# DM1097_IMX378.net
KiCad netlist of a schematic drawn in Altium Designer
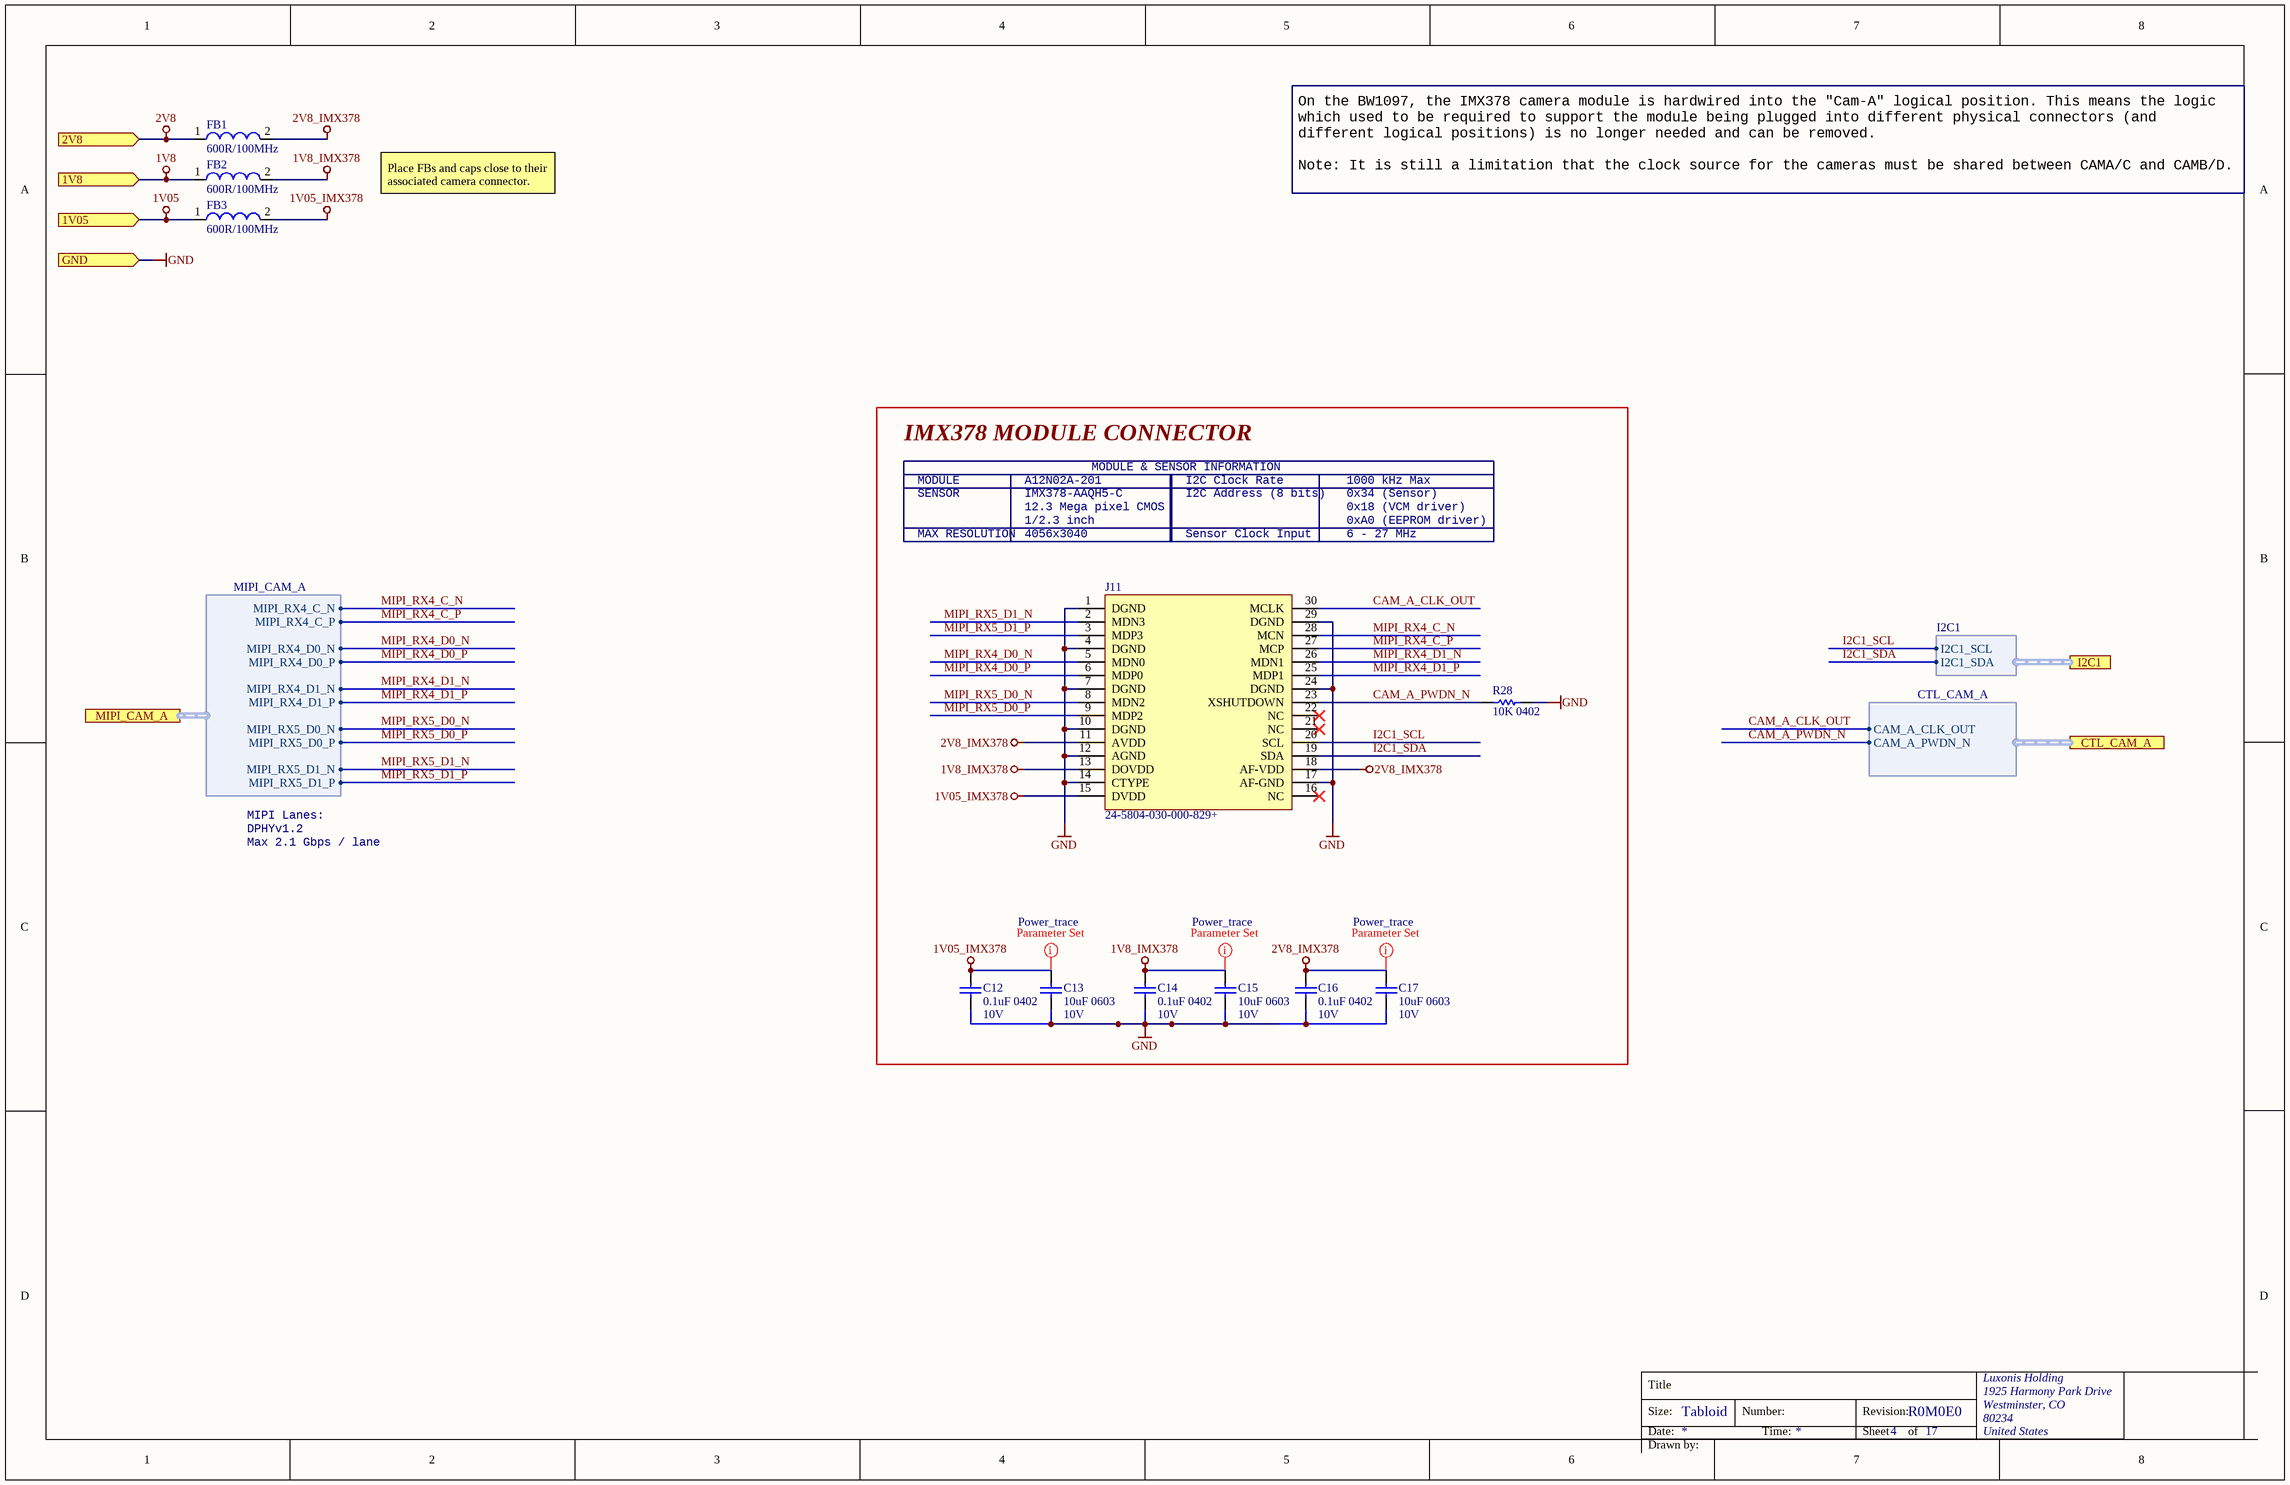
[diagram p0: DM1097_IMX378.SchDoc]

(export (version "E")
  (design (tool "Eeschema 10.0.6"))
  (components
    (comp (ref "C12")
      (value "0.1uF 0402")
      (footprint "CAP_Altium_Vault_Generic:CAPC0402(1005)70_N")
      (description "CAP CER 0.1UF 10V X7R 0402 5%")
      (fields (field (name "TOLERANCE") "5%") (field (name "VOLTAGE RATING") "10V"))
      (libsource (lib "LuxonisMaster") (part "GRM155R71A104JA01D"))
    )
    (comp (ref "C13")
      (value "10uF 0603")
      (footprint "CAP_Altium_Vault_Generic:CAPC0603(1608)100_N")
      (description "CAP CER 10UF 10V X5R 0603 20%")
      (fields (field (name "TOLERANCE") "20%") (field (name "VOLTAGE RATING") "10V"))
      (libsource (lib "LuxonisMaster") (part "GRM188R61A106ME69D"))
    )
    (comp (ref "C14")
      (value "0.1uF 0402")
      (footprint "CAP_Altium_Vault_Generic:CAPC0402(1005)70_N")
      (description "CAP CER 0.1UF 10V X7R 0402 5%")
      (fields (field (name "TOLERANCE") "5%") (field (name "VOLTAGE RATING") "10V"))
      (libsource (lib "LuxonisMaster") (part "GRM155R71A104JA01D"))
    )
    (comp (ref "C15")
      (value "10uF 0603")
      (footprint "CAP_Altium_Vault_Generic:CAPC0603(1608)100_N")
      (description "CAP CER 10UF 10V X5R 0603 20%")
      (fields (field (name "TOLERANCE") "20%") (field (name "VOLTAGE RATING") "10V"))
      (libsource (lib "LuxonisMaster") (part "GRM188R61A106ME69D"))
    )
    (comp (ref "C16")
      (value "0.1uF 0402")
      (footprint "CAP_Altium_Vault_Generic:CAPC0402(1005)70_N")
      (description "CAP CER 0.1UF 10V X7R 0402 5%")
      (fields (field (name "TOLERANCE") "5%") (field (name "VOLTAGE RATING") "10V"))
      (libsource (lib "LuxonisMaster") (part "GRM155R71A104JA01D"))
    )
    (comp (ref "C17")
      (value "10uF 0603")
      (footprint "CAP_Altium_Vault_Generic:CAPC0603(1608)100_N")
      (description "CAP CER 10UF 10V X5R 0603 20%")
      (fields (field (name "TOLERANCE") "20%") (field (name "VOLTAGE RATING") "10V"))
      (libsource (lib "LuxonisMaster") (part "GRM188R61A106ME69D"))
    )
    (comp (ref "FB1")
      (value "600R/100MHz")
      (footprint "LuxonisMaster:2508056017Y2")
      (description "FERRITE BEAD, 0.1OHM, 2A, 0805, 600R/100MHz")
      (fields (field (name "TOLERANCE") "25%"))
      (libsource (lib "LuxonisMaster") (part "2508056017Y2"))
    )
    (comp (ref "FB2")
      (value "600R/100MHz")
      (footprint "LuxonisMaster:2508056017Y2")
      (description "FERRITE BEAD, 0.1OHM, 2A, 0805, 600R/100MHz")
      (fields (field (name "TOLERANCE") "25%"))
      (libsource (lib "LuxonisMaster") (part "2508056017Y2"))
    )
    (comp (ref "FB3")
      (value "600R/100MHz")
      (footprint "LuxonisMaster:2508056017Y2")
      (description "FERRITE BEAD, 0.1OHM, 2A, 0805, 600R/100MHz")
      (fields (field (name "TOLERANCE") "25%"))
      (libsource (lib "LuxonisMaster") (part "2508056017Y2"))
    )
    (comp (ref "J11")
      (value "24-5804-030-000-829+")
      (footprint "LuxonisMaster:A12N02A-201_MatedModule")
      (description "CONN Series 5804 board to board 0.4mm pitch 30 way connector")
      (libsource (lib "LuxonisMaster") (part "A12N02A-201_Connector"))
    )
    (comp (ref "R28")
      (value "10K 0402")
      (footprint "RES_Altium_Vault_Generic:RESC0402(1005)_N")
      (fields (field (name "TOLERANCE") "1%"))
      (libsource (lib "LuxonisMaster") (part "RC0402FR-1310KL"))
    )
  )
  (nets
    (net (code "4") (name "/CAM_A_CLK_OUT") (class "Default")
      (node (ref "J11") (pin "30") (pinfunction "MCLK_30") (pintype "passive"))
    )
    (net (code "5") (name "/CAM_A_PWDN_N") (class "Default")
      (node (ref "J11") (pin "23") (pinfunction "XSHUTDOWN_23") (pintype "passive"))
      (node (ref "R28") (pin "1") (pinfunction "1_1") (pintype "passive"))
    )
    (net (code "6") (name "/I2C1_SCL") (class "Default")
      (node (ref "J11") (pin "20") (pinfunction "SCL_20") (pintype "passive"))
    )
    (net (code "7") (name "/I2C1_SDA") (class "Default")
      (node (ref "J11") (pin "19") (pinfunction "SDA_19") (pintype "passive"))
    )
    (net (code "8") (name "/MIPI_RX4_C_N") (class "Default")
      (node (ref "J11") (pin "28") (pinfunction "MCN_28") (pintype "passive"))
    )
    (net (code "9") (name "/MIPI_RX4_C_P") (class "Default")
      (node (ref "J11") (pin "27") (pinfunction "MCP_27") (pintype "passive"))
    )
    (net (code "10") (name "/MIPI_RX4_D0_N") (class "Default")
      (node (ref "J11") (pin "5") (pinfunction "MDN0_5") (pintype "passive"))
    )
    (net (code "11") (name "/MIPI_RX4_D0_P") (class "Default")
      (node (ref "J11") (pin "6") (pinfunction "MDP0_6") (pintype "passive"))
    )
    (net (code "12") (name "/MIPI_RX4_D1_N") (class "Default")
      (node (ref "J11") (pin "26") (pinfunction "MDN1_26") (pintype "passive"))
    )
    (net (code "13") (name "/MIPI_RX4_D1_P") (class "Default")
      (node (ref "J11") (pin "25") (pinfunction "MDP1_25") (pintype "passive"))
    )
    (net (code "14") (name "/MIPI_RX5_D0_N") (class "Default")
      (node (ref "J11") (pin "8") (pinfunction "MDN2_8") (pintype "passive"))
    )
    (net (code "15") (name "/MIPI_RX5_D0_P") (class "Default")
      (node (ref "J11") (pin "9") (pinfunction "MDP2_9") (pintype "passive"))
    )
    (net (code "16") (name "/MIPI_RX5_D1_N") (class "Default")
      (node (ref "J11") (pin "2") (pinfunction "MDN3_2") (pintype "passive"))
    )
    (net (code "17") (name "/MIPI_RX5_D1_P") (class "Default")
      (node (ref "J11") (pin "3") (pinfunction "MDP3_3") (pintype "passive"))
    )
    (net (code "21") (name "1V05") (class "Default")
      (node (ref "FB3") (pin "1") (pinfunction "1_1") (pintype "passive"))
    )
    (net (code "22") (name "1V05_IMX378") (class "Default")
      (node (ref "C12") (pin "2") (pinfunction "2_2") (pintype "passive"))
      (node (ref "C13") (pin "2") (pinfunction "2_2") (pintype "passive"))
      (node (ref "FB3") (pin "2") (pinfunction "2_2") (pintype "passive"))
      (node (ref "J11") (pin "15") (pinfunction "DVDD_15") (pintype "passive"))
    )
    (net (code "23") (name "1V8") (class "Default")
      (node (ref "FB2") (pin "1") (pinfunction "1_1") (pintype "passive"))
    )
    (net (code "24") (name "1V8_IMX378") (class "Default")
      (node (ref "C14") (pin "2") (pinfunction "2_2") (pintype "passive"))
      (node (ref "C15") (pin "2") (pinfunction "2_2") (pintype "passive"))
      (node (ref "FB2") (pin "2") (pinfunction "2_2") (pintype "passive"))
      (node (ref "J11") (pin "13") (pinfunction "DOVDD_13") (pintype "passive"))
    )
    (net (code "25") (name "2V8") (class "Default")
      (node (ref "FB1") (pin "1") (pinfunction "1_1") (pintype "passive"))
    )
    (net (code "26") (name "2V8_IMX378") (class "Default")
      (node (ref "C16") (pin "2") (pinfunction "2_2") (pintype "passive"))
      (node (ref "C17") (pin "2") (pinfunction "2_2") (pintype "passive"))
      (node (ref "FB1") (pin "2") (pinfunction "2_2") (pintype "passive"))
      (node (ref "J11") (pin "11") (pinfunction "AVDD_11") (pintype "passive"))
      (node (ref "J11") (pin "18") (pinfunction "AF-VDD_18") (pintype "passive"))
    )
    (net (code "27") (name "GND") (class "Default")
      (node (ref "C12") (pin "1") (pinfunction "1_1") (pintype "passive"))
      (node (ref "C13") (pin "1") (pinfunction "1_1") (pintype "passive"))
      (node (ref "C14") (pin "1") (pinfunction "1_1") (pintype "passive"))
      (node (ref "C15") (pin "1") (pinfunction "1_1") (pintype "passive"))
      (node (ref "C16") (pin "1") (pinfunction "1_1") (pintype "passive"))
      (node (ref "C17") (pin "1") (pinfunction "1_1") (pintype "passive"))
      (node (ref "J11") (pin "1") (pinfunction "DGND_1") (pintype "passive"))
      (node (ref "J11") (pin "10") (pinfunction "DGND_10") (pintype "passive"))
      (node (ref "J11") (pin "12") (pinfunction "AGND_12") (pintype "passive"))
      (node (ref "J11") (pin "14") (pinfunction "CTYPE_14") (pintype "passive"))
      (node (ref "J11") (pin "17") (pinfunction "AF-GND_17") (pintype "passive"))
      (node (ref "J11") (pin "24") (pinfunction "DGND_24") (pintype "passive"))
      (node (ref "J11") (pin "29") (pinfunction "DGND_29") (pintype "passive"))
      (node (ref "J11") (pin "4") (pinfunction "DGND_4") (pintype "passive"))
      (node (ref "J11") (pin "7") (pinfunction "DGND_7") (pintype "passive"))
      (node (ref "R28") (pin "2") (pinfunction "2_2") (pintype "passive"))
    )
    (net (code "28") (name "unconnected-(J11-NC-Pad16)") (class "Default")
      (node (ref "J11") (pin "16") (pinfunction "NC_16") (pintype "passive+no_connect"))
    )
    (net (code "29") (name "unconnected-(J11-NC-Pad21)") (class "Default")
      (node (ref "J11") (pin "21") (pinfunction "NC_21") (pintype "passive+no_connect"))
    )
    (net (code "30") (name "unconnected-(J11-NC-Pad22)") (class "Default")
      (node (ref "J11") (pin "22") (pinfunction "NC_22") (pintype "passive+no_connect"))
    )
  )
)
